# Encoder.net
KiCad netlist of a schematic drawn in Altium Designer
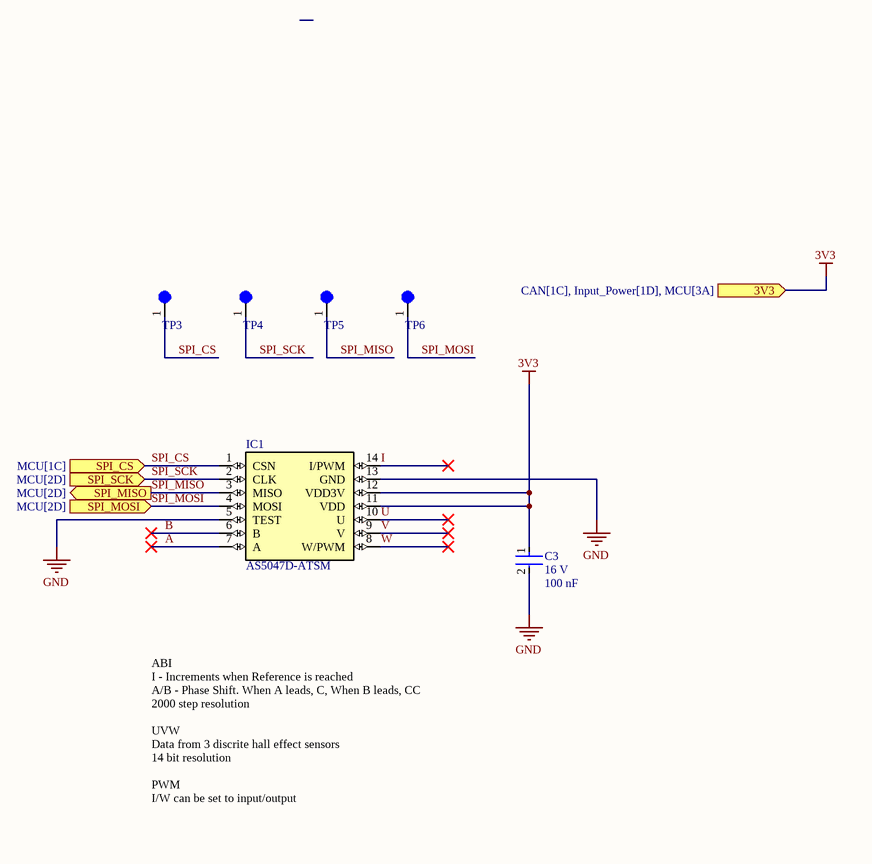
[diagram p0: Encoder.SchDoc]

(export (version "E")
  (design (tool "Eeschema 10.0.6"))
  (components
    (comp (ref "C3")
      (value "CC0402KRX7R7BB104")
      (footprint "CAP-0402")
      (description "CAP CER 0.1UF 16V X7R 0402")
      (fields (field (name "VOLTAGE RATING") "16 V") (field (name "CAPACITANCE") "100 nF"))
      (libsource (lib "JLC_25") (part "CAP-0.1U-0001"))
    )
    (comp (ref "IC1")
      (value "AS5047D-ATSM")
      (footprint "SOP65P640X110-14N")
      (description "Hall Effect Sensor Rotary Position External Magnet, Not Included Gull Wing")
      (fields (field (name "MF") "ams"))
      (libsource (lib "MasterLib") (part "IC-ABSENC-0001"))
    )
    (comp (ref "TP3")
      (value "5003")
      (footprint "TEST02")
      (description "Surface Mount")
      (libsource (lib "JLC_25") (part "TEST-POINT-0002"))
    )
    (comp (ref "TP4")
      (value "5003")
      (footprint "TEST02")
      (description "Surface Mount")
      (libsource (lib "JLC_25") (part "TEST-POINT-0002"))
    )
    (comp (ref "TP5")
      (value "5003")
      (footprint "TEST02")
      (description "Surface Mount")
      (libsource (lib "JLC_25") (part "TEST-POINT-0002"))
    )
    (comp (ref "TP6")
      (value "5003")
      (footprint "TEST02")
      (description "Surface Mount")
      (libsource (lib "JLC_25") (part "TEST-POINT-0002"))
    )
  )
  (nets
    (net (code "1") (name "/A") (class "Default")
      (node (ref "IC1") (pin "7") (pinfunction "A_7") (pintype "bidirectional+no_connect"))
    )
    (net (code "2") (name "/B") (class "Default")
      (node (ref "IC1") (pin "6") (pinfunction "B_6") (pintype "bidirectional+no_connect"))
    )
    (net (code "3") (name "/I") (class "Default")
      (node (ref "IC1") (pin "14") (pinfunction "I/PWM_14") (pintype "bidirectional+no_connect"))
    )
    (net (code "4") (name "/SPI_CS") (class "Default")
      (node (ref "IC1") (pin "1") (pinfunction "CSN_1") (pintype "bidirectional"))
      (node (ref "TP3") (pin "1") (pinfunction "0_1") (pintype "passive"))
    )
    (net (code "5") (name "/SPI_MISO") (class "Default")
      (node (ref "IC1") (pin "3") (pinfunction "MISO_3") (pintype "bidirectional"))
      (node (ref "TP5") (pin "1") (pinfunction "0_1") (pintype "passive"))
    )
    (net (code "6") (name "/SPI_MOSI") (class "Default")
      (node (ref "IC1") (pin "4") (pinfunction "MOSI_4") (pintype "bidirectional"))
      (node (ref "TP6") (pin "1") (pinfunction "0_1") (pintype "passive"))
    )
    (net (code "7") (name "/SPI_SCK") (class "Default")
      (node (ref "IC1") (pin "2") (pinfunction "CLK_2") (pintype "bidirectional"))
      (node (ref "TP4") (pin "1") (pinfunction "0_1") (pintype "passive"))
    )
    (net (code "8") (name "/U") (class "Default")
      (node (ref "IC1") (pin "10") (pinfunction "U_10") (pintype "bidirectional+no_connect"))
    )
    (net (code "9") (name "/V") (class "Default")
      (node (ref "IC1") (pin "9") (pinfunction "V_9") (pintype "bidirectional+no_connect"))
    )
    (net (code "10") (name "/W") (class "Default")
      (node (ref "IC1") (pin "8") (pinfunction "W/PWM_8") (pintype "bidirectional+no_connect"))
    )
    (net (code "11") (name "3V3") (class "Default")
      (node (ref "C3") (pin "1") (pinfunction "1_1") (pintype "passive"))
      (node (ref "IC1") (pin "11") (pinfunction "VDD_11") (pintype "bidirectional"))
      (node (ref "IC1") (pin "12") (pinfunction "VDD3V_12") (pintype "bidirectional"))
    )
    (net (code "12") (name "GND") (class "Default")
      (node (ref "C3") (pin "2") (pinfunction "2_2") (pintype "passive"))
      (node (ref "IC1") (pin "13") (pinfunction "GND_13") (pintype "bidirectional"))
      (node (ref "IC1") (pin "5") (pinfunction "TEST_5") (pintype "bidirectional"))
    )
  )
)
